# GDEnvSensorNode_1_4g.net
KiCad netlist of a schematic drawn in EAGLE
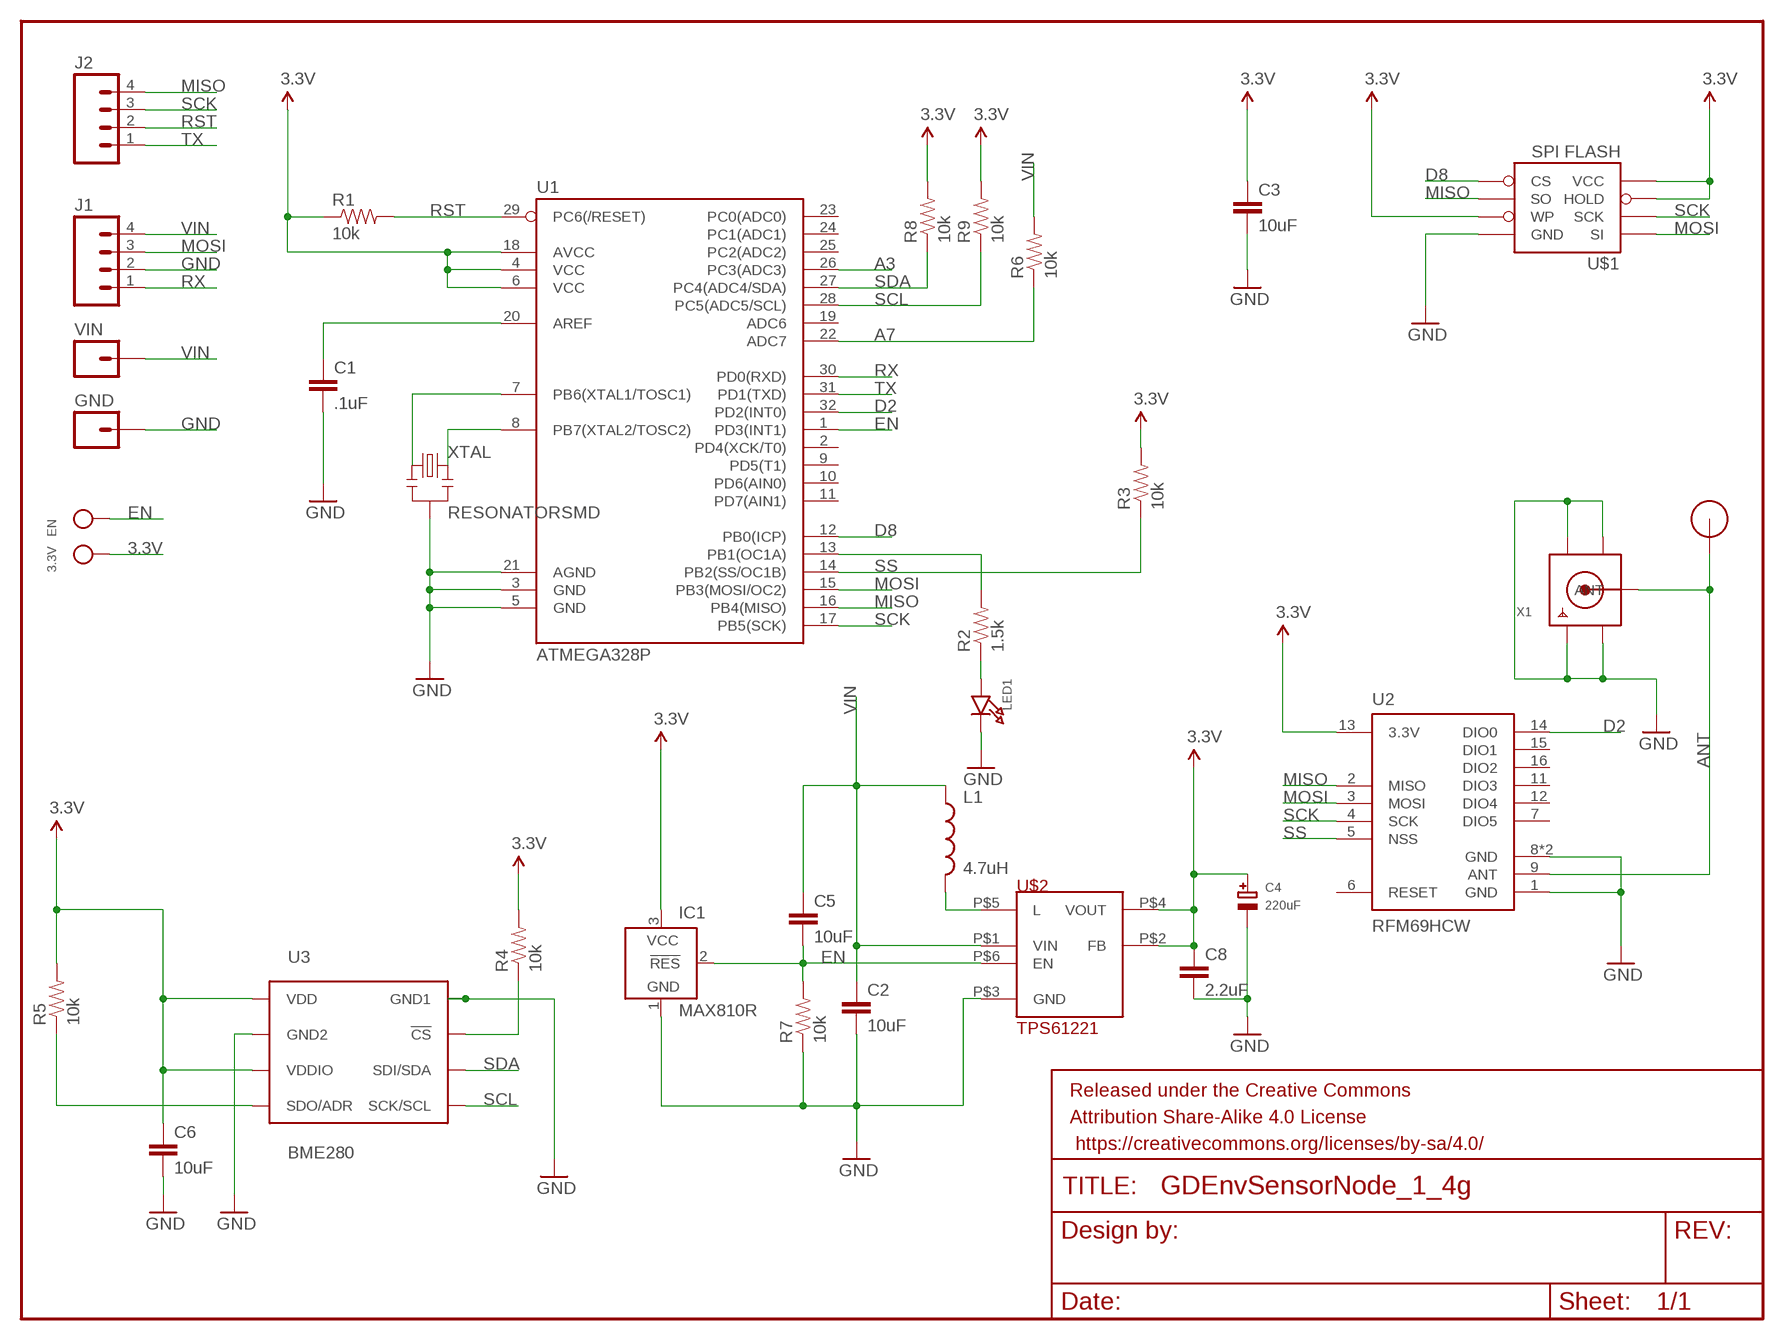
[diagram p0: schematic, sheet 1]

(export (version "E")
  (design (tool "Eeschema 10.0.6"))
  (components
    (comp (ref "3.3V")
      (value "TESTPOINTROUND1MM")
      (footprint "eagle-import:TESTPOINT_ROUND_1MM")
      (libsource (lib "eagle-import") (part "TESTPOINTROUND1MM"))
    )
    (comp (ref "C1")
      (value ".1uF")
      (footprint "eagle-import:0805")
      (libsource (lib "eagle-import") (part "CAP0805"))
    )
    (comp (ref "C2")
      (value "10uF")
      (footprint "eagle-import:0805")
      (libsource (lib "eagle-import") (part "CAP0805"))
    )
    (comp (ref "C3")
      (value "10uF")
      (footprint "eagle-import:0805")
      (libsource (lib "eagle-import") (part "CAP0805"))
    )
    (comp (ref "C4")
      (value "220uF")
      (footprint "eagle-import:EIA7343-31_D-R")
      (libsource (lib "eagle-import") (part "CAP_TANTALUMD/7343_REFLOW"))
    )
    (comp (ref "C5")
      (value "10uF")
      (footprint "eagle-import:0805")
      (libsource (lib "eagle-import") (part "CAP0805"))
    )
    (comp (ref "C6")
      (value "10uF")
      (footprint "eagle-import:0805")
      (libsource (lib "eagle-import") (part "CAP0805"))
    )
    (comp (ref "C8")
      (value "2.2uF")
      (footprint "eagle-import:0805")
      (libsource (lib "eagle-import") (part "CAP0805"))
    )
    (comp (ref "EN")
      (value "TESTPOINTROUND1MM")
      (footprint "eagle-import:TESTPOINT_ROUND_1MM")
      (libsource (lib "eagle-import") (part "TESTPOINTROUND1MM"))
    )
    (comp (ref "FRAME1")
      (value "FRAME-LETTER")
      (footprint "eagle-import:CREATIVE_COMMONS")
      (libsource (lib "eagle-import") (part "FRAME-LETTER"))
    )
    (comp (ref "GND")
      (value "M01PTH_2MM")
      (footprint "eagle-import:1X01_2MM")
      (libsource (lib "eagle-import") (part "M01PTH_2MM"))
    )
    (comp (ref "IC1")
      (value "MAX810R")
      (footprint "eagle-import:SOT23B-3")
      (fields (field (name "MF") "MICROCHIP") (field (name "MPN") "TCM809MENB713"))
      (libsource (lib "eagle-import") (part "TCM809"))
    )
    (comp (ref "J1")
      (value "M04PTH")
      (footprint "eagle-import:1X04")
      (libsource (lib "eagle-import") (part "M04PTH"))
    )
    (comp (ref "J2")
      (value "M04PTH")
      (footprint "eagle-import:1X04")
      (libsource (lib "eagle-import") (part "M04PTH"))
    )
    (comp (ref "L1")
      (value "4.7uH")
      (footprint "eagle-import:1210")
      (libsource (lib "eagle-import") (part "INDUCTOR1210"))
    )
    (comp (ref "LED1")
      (value "LED0805")
      (footprint "eagle-import:CHIPLED_0805")
      (libsource (lib "eagle-import") (part "LED0805"))
    )
    (comp (ref "R1")
      (value "10k")
      (footprint "eagle-import:0805")
      (libsource (lib "eagle-import") (part "RESISTOR0805-RES"))
    )
    (comp (ref "R2")
      (value "1.5k")
      (footprint "eagle-import:0805")
      (libsource (lib "eagle-import") (part "RESISTOR0805-RES"))
    )
    (comp (ref "R3")
      (value "10k")
      (footprint "eagle-import:0805")
      (libsource (lib "eagle-import") (part "RESISTOR0805-RES"))
    )
    (comp (ref "R4")
      (value "10k")
      (footprint "eagle-import:0805")
      (libsource (lib "eagle-import") (part "RESISTOR0805-RES"))
    )
    (comp (ref "R5")
      (value "10k")
      (footprint "eagle-import:0805")
      (libsource (lib "eagle-import") (part "RESISTOR0805-RES"))
    )
    (comp (ref "R6")
      (value "10k")
      (footprint "eagle-import:0805")
      (libsource (lib "eagle-import") (part "RESISTOR0805-RES"))
    )
    (comp (ref "R7")
      (value "10k")
      (footprint "eagle-import:0805")
      (libsource (lib "eagle-import") (part "RESISTOR0805-RES"))
    )
    (comp (ref "R8")
      (value "10k")
      (footprint "eagle-import:0805")
      (libsource (lib "eagle-import") (part "RESISTOR0805-RES"))
    )
    (comp (ref "R9")
      (value "10k")
      (footprint "eagle-import:0805")
      (libsource (lib "eagle-import") (part "RESISTOR0805-RES"))
    )
    (comp (ref "U$1")
      (value "SPI FLASH")
      (footprint "eagle-import:SO08")
      (libsource (lib "eagle-import") (part "AT25F512BJEDEC_3.9MM"))
    )
    (comp (ref "U$2")
      (value "TPS61221")
      (footprint "eagle-import:TPS61221")
      (fields (field (name "MF") "Texas Instruments"))
      (libsource (lib "eagle-import") (part "TPS61221"))
    )
    (comp (ref "U$4")
      (value "RFM12B_ANTENNA")
      (footprint "eagle-import:RFM12B-ANTENNA")
      (libsource (lib "eagle-import") (part "RFM12B_ANTENNA"))
    )
    (comp (ref "U1")
      (value "ATMEGA328P")
      (footprint "eagle-import:TQFP32-08")
      (libsource (lib "eagle-import") (part "ATMEGA328P_TQFP"))
    )
    (comp (ref "U2")
      (value "RFM69HCW")
      (footprint "eagle-import:RFM69HCW-XXXS2")
      (libsource (lib "eagle-import") (part "RFM69HCW"))
    )
    (comp (ref "U3")
      (value "BME280")
      (footprint "eagle-import:BME280_LGA")
      (libsource (lib "eagle-import") (part "BME280"))
    )
    (comp (ref "VIN")
      (value "M01PTH_2MM")
      (footprint "eagle-import:1X01_2MM")
      (libsource (lib "eagle-import") (part "M01PTH_2MM"))
    )
    (comp (ref "X1")
      (value "SMACONNECTOR_EDGE_UFL")
      (footprint "eagle-import:SMA_EDGELAUNCH_UFL")
      (libsource (lib "eagle-import") (part "SMACONNECTOR_EDGE_UFL"))
    )
    (comp (ref "XTAL")
      (value "RESONATORSMD")
      (footprint "eagle-import:RESONATOR-SMD")
      (libsource (lib "eagle-import") (part "RESONATORSMD"))
    )
  )
  (nets
    (net (code "1") (name "/A3") (class "Default")
      (node (ref "U1") (pin "26") (pinfunction "PC3(ADC3)_26") (pintype "bidirectional"))
    )
    (net (code "2") (name "/A7") (class "Default")
      (node (ref "R6") (pin "1") (pinfunction "1_1") (pintype "passive"))
      (node (ref "U1") (pin "22") (pinfunction "ADC7_22") (pintype "bidirectional"))
    )
    (net (code "3") (name "/ANT") (class "Default")
      (node (ref "U$4") (pin "P$1") (pinfunction "1_P$1") (pintype "bidirectional"))
      (node (ref "U2") (pin "9") (pinfunction "ANT_9") (pintype "passive"))
      (node (ref "X1") (pin "P") (pinfunction "ANT_P") (pintype "bidirectional"))
    )
    (net (code "4") (name "/D2") (class "Default")
      (node (ref "U1") (pin "32") (pinfunction "PD2(INT0)_32") (pintype "bidirectional"))
      (node (ref "U2") (pin "14") (pinfunction "DIO0_14") (pintype "bidirectional"))
    )
    (net (code "5") (name "/D8") (class "Default")
      (node (ref "U$1") (pin "1_CS") (pinfunction "CS_1_CS") (pintype "bidirectional"))
      (node (ref "U1") (pin "12") (pinfunction "PB0(ICP)_12") (pintype "bidirectional"))
    )
    (net (code "6") (name "/EN") (class "Default")
      (node (ref "C5") (pin "2") (pinfunction "2_2") (pintype "passive"))
      (node (ref "EN") (pin "P$1") (pinfunction "P$1_P$1") (pintype "bidirectional"))
      (node (ref "IC1") (pin "2") (pinfunction "~{RES}_2") (pintype "output"))
      (node (ref "R7") (pin "2") (pinfunction "2_2") (pintype "passive"))
      (node (ref "U$2") (pin "P$6") (pinfunction "EN_P$6") (pintype "bidirectional"))
      (node (ref "U1") (pin "1") (pinfunction "PD3(INT1)_1") (pintype "bidirectional"))
    )
    (net (code "7") (name "/MISO") (class "Default")
      (node (ref "J2") (pin "4") (pinfunction "4_4") (pintype "passive"))
      (node (ref "U$1") (pin "2_SO") (pinfunction "SO_2_SO") (pintype "bidirectional"))
      (node (ref "U1") (pin "16") (pinfunction "PB4(MISO)_16") (pintype "bidirectional"))
      (node (ref "U2") (pin "2") (pinfunction "MISO_2") (pintype "bidirectional"))
    )
    (net (code "8") (name "/MOSI") (class "Default")
      (node (ref "J1") (pin "3") (pinfunction "3_3") (pintype "passive"))
      (node (ref "U$1") (pin "5_SI") (pinfunction "SI_5_SI") (pintype "bidirectional"))
      (node (ref "U1") (pin "15") (pinfunction "PB3(MOSI/OC2)_15") (pintype "bidirectional"))
      (node (ref "U2") (pin "3") (pinfunction "MOSI_3") (pintype "input"))
    )
    (net (code "9") (name "/RST") (class "Default")
      (node (ref "J2") (pin "2") (pinfunction "2_2") (pintype "passive"))
      (node (ref "R1") (pin "2") (pinfunction "2_2") (pintype "passive"))
      (node (ref "U1") (pin "29") (pinfunction "PC6(/RESET)_29") (pintype "bidirectional"))
    )
    (net (code "10") (name "/RX") (class "Default")
      (node (ref "J1") (pin "1") (pinfunction "1_1") (pintype "passive"))
      (node (ref "U1") (pin "30") (pinfunction "PD0(RXD)_30") (pintype "bidirectional"))
    )
    (net (code "11") (name "/SCK") (class "Default")
      (node (ref "J2") (pin "3") (pinfunction "3_3") (pintype "passive"))
      (node (ref "U$1") (pin "6_SCK") (pinfunction "SCK_6_SCK") (pintype "bidirectional"))
      (node (ref "U1") (pin "17") (pinfunction "PB5(SCK)_17") (pintype "bidirectional"))
      (node (ref "U2") (pin "4") (pinfunction "SCK_4") (pintype "input"))
    )
    (net (code "12") (name "/SCL") (class "Default")
      (node (ref "R9") (pin "1") (pinfunction "1_1") (pintype "passive"))
      (node (ref "U1") (pin "28") (pinfunction "PC5(ADC5/SCL)_28") (pintype "bidirectional"))
      (node (ref "U3") (pin "P$4") (pinfunction "SCK/SCL_P$4") (pintype "bidirectional"))
    )
    (net (code "13") (name "/SDA") (class "Default")
      (node (ref "R8") (pin "1") (pinfunction "1_1") (pintype "passive"))
      (node (ref "U1") (pin "27") (pinfunction "PC4(ADC4/SDA)_27") (pintype "bidirectional"))
      (node (ref "U3") (pin "P$3") (pinfunction "SDI/SDA_P$3") (pintype "bidirectional"))
    )
    (net (code "14") (name "/SS") (class "Default")
      (node (ref "R3") (pin "1") (pinfunction "1_1") (pintype "passive"))
      (node (ref "U1") (pin "14") (pinfunction "PB2(SS/OC1B)_14") (pintype "bidirectional"))
      (node (ref "U2") (pin "5") (pinfunction "NSS_5") (pintype "input"))
    )
    (net (code "15") (name "/TX") (class "Default")
      (node (ref "J2") (pin "1") (pinfunction "1_1") (pintype "passive"))
      (node (ref "U1") (pin "31") (pinfunction "PD1(TXD)_31") (pintype "bidirectional"))
    )
    (net (code "16") (name "/VIN") (class "Default")
      (node (ref "C2") (pin "1") (pinfunction "1_1") (pintype "passive"))
      (node (ref "C5") (pin "1") (pinfunction "1_1") (pintype "passive"))
      (node (ref "J1") (pin "4") (pinfunction "4_4") (pintype "passive"))
      (node (ref "L1") (pin "1") (pinfunction "1_1") (pintype "passive"))
      (node (ref "R6") (pin "2") (pinfunction "2_2") (pintype "passive"))
      (node (ref "U$2") (pin "P$1") (pinfunction "VIN_P$1") (pintype "bidirectional"))
      (node (ref "VIN") (pin "1") (pinfunction "1_1") (pintype "passive"))
    )
    (net (code "17") (name "3.3V") (class "Default")
      (node (ref "3.3V") (pin "P$1") (pinfunction "P$1_P$1") (pintype "bidirectional"))
      (node (ref "C3") (pin "1") (pinfunction "1_1") (pintype "passive"))
      (node (ref "C4") (pin "+") (pinfunction "+_+") (pintype "passive"))
      (node (ref "C6") (pin "1") (pinfunction "1_1") (pintype "passive"))
      (node (ref "C8") (pin "1") (pinfunction "1_1") (pintype "passive"))
      (node (ref "IC1") (pin "3") (pinfunction "VCC_3") (pintype "power_in"))
      (node (ref "R1") (pin "1") (pinfunction "1_1") (pintype "passive"))
      (node (ref "R3") (pin "2") (pinfunction "2_2") (pintype "passive"))
      (node (ref "R4") (pin "2") (pinfunction "2_2") (pintype "passive"))
      (node (ref "R5") (pin "2") (pinfunction "2_2") (pintype "passive"))
      (node (ref "R8") (pin "2") (pinfunction "2_2") (pintype "passive"))
      (node (ref "R9") (pin "2") (pinfunction "2_2") (pintype "passive"))
      (node (ref "U$1") (pin "3_WP") (pinfunction "WP_3_WP") (pintype "bidirectional"))
      (node (ref "U$1") (pin "7_HOLD") (pinfunction "HOLD_7_HOLD") (pintype "bidirectional"))
      (node (ref "U$1") (pin "8_VCC") (pinfunction "VCC_8_VCC") (pintype "bidirectional"))
      (node (ref "U$2") (pin "P$2") (pinfunction "FB_P$2") (pintype "bidirectional"))
      (node (ref "U$2") (pin "P$4") (pinfunction "VOUT_P$4") (pintype "bidirectional"))
      (node (ref "U1") (pin "18") (pinfunction "AVCC_18") (pintype "bidirectional"))
      (node (ref "U1") (pin "4") (pinfunction "VCC_4") (pintype "bidirectional"))
      (node (ref "U1") (pin "6") (pinfunction "VCC_6") (pintype "bidirectional"))
      (node (ref "U2") (pin "13") (pinfunction "3.3V_13") (pintype "power_in"))
      (node (ref "U3") (pin "P$6") (pinfunction "VDDIO_P$6") (pintype "bidirectional"))
      (node (ref "U3") (pin "P$8") (pinfunction "VDD_P$8") (pintype "bidirectional"))
    )
    (net (code "18") (name "GND") (class "Default")
      (node (ref "C1") (pin "2") (pinfunction "2_2") (pintype "passive"))
      (node (ref "C2") (pin "2") (pinfunction "2_2") (pintype "passive"))
      (node (ref "C3") (pin "2") (pinfunction "2_2") (pintype "passive"))
      (node (ref "C4") (pin "-") (pinfunction "-_-") (pintype "passive"))
      (node (ref "C6") (pin "2") (pinfunction "2_2") (pintype "passive"))
      (node (ref "C8") (pin "2") (pinfunction "2_2") (pintype "passive"))
      (node (ref "GND") (pin "1") (pinfunction "1_1") (pintype "passive"))
      (node (ref "IC1") (pin "1") (pinfunction "GND_1") (pintype "power_in"))
      (node (ref "J1") (pin "2") (pinfunction "2_2") (pintype "passive"))
      (node (ref "LED1") (pin "C") (pinfunction "C_C") (pintype "passive"))
      (node (ref "R7") (pin "1") (pinfunction "1_1") (pintype "passive"))
      (node (ref "U$1") (pin "4_GND") (pinfunction "GND_4_GND") (pintype "bidirectional"))
      (node (ref "U$2") (pin "P$3") (pinfunction "GND_P$3") (pintype "bidirectional"))
      (node (ref "U1") (pin "21") (pinfunction "AGND_21") (pintype "bidirectional"))
      (node (ref "U1") (pin "3") (pinfunction "GND_3") (pintype "bidirectional"))
      (node (ref "U1") (pin "5") (pinfunction "GND_5") (pintype "bidirectional"))
      (node (ref "U2") (pin "1") (pinfunction "GND_1") (pintype "power_in"))
      (node (ref "U2") (pin "10") (pinfunction "GND_10") (pintype "power_in"))
      (node (ref "U2") (pin "8") (pinfunction "GND_8") (pintype "power_in"))
      (node (ref "U3") (pin "P$1") (pinfunction "GND1_P$1") (pintype "bidirectional"))
      (node (ref "U3") (pin "P$7") (pinfunction "GND2_P$7") (pintype "bidirectional"))
      (node (ref "X1") (pin "GND@1") (pinfunction "GND1_GND@1") (pintype "power_in"))
      (node (ref "X1") (pin "GND@2") (pinfunction "GND2_GND@2") (pintype "power_in"))
      (node (ref "X1") (pin "GND@3") (pinfunction "GND3_GND@3") (pintype "power_in"))
      (node (ref "X1") (pin "GND@4") (pinfunction "GND4_GND@4") (pintype "power_in"))
      (node (ref "XTAL") (pin "2") (pinfunction "2_2") (pintype "passive"))
    )
    (net (code "19") (name "Net-(LED1-PadA)") (class "Default")
      (node (ref "LED1") (pin "A") (pinfunction "A_A") (pintype "passive"))
      (node (ref "R2") (pin "1") (pinfunction "1_1") (pintype "passive"))
    )
    (net (code "20") (name "Net-(U$2-L)") (class "Default")
      (node (ref "L1") (pin "2") (pinfunction "2_2") (pintype "passive"))
      (node (ref "U$2") (pin "P$5") (pinfunction "L_P$5") (pintype "bidirectional"))
    )
    (net (code "21") (name "Net-(U1-AREF)") (class "Default")
      (node (ref "C1") (pin "1") (pinfunction "1_1") (pintype "passive"))
      (node (ref "U1") (pin "20") (pinfunction "AREF_20") (pintype "bidirectional"))
    )
    (net (code "22") (name "Net-(U1-PB1(OC1A))") (class "Default")
      (node (ref "R2") (pin "2") (pinfunction "2_2") (pintype "passive"))
      (node (ref "U1") (pin "13") (pinfunction "PB1(OC1A)_13") (pintype "bidirectional"))
    )
    (net (code "23") (name "Net-(U1-PB6(XTAL1{slash}TOSC1))") (class "Default")
      (node (ref "U1") (pin "7") (pinfunction "PB6(XTAL1/TOSC1)_7") (pintype "bidirectional"))
      (node (ref "XTAL") (pin "1") (pinfunction "1_1") (pintype "passive"))
    )
    (net (code "24") (name "Net-(U1-PB7(XTAL2{slash}TOSC2))") (class "Default")
      (node (ref "U1") (pin "8") (pinfunction "PB7(XTAL2/TOSC2)_8") (pintype "bidirectional"))
      (node (ref "XTAL") (pin "3") (pinfunction "3_3") (pintype "passive"))
    )
    (net (code "25") (name "Net-(U3-SDO{slash}ADR)") (class "Default")
      (node (ref "R5") (pin "1") (pinfunction "1_1") (pintype "passive"))
      (node (ref "U3") (pin "P$5") (pinfunction "SDO/ADR_P$5") (pintype "bidirectional"))
    )
    (net (code "26") (name "Net-(U3-~{CS})") (class "Default")
      (node (ref "R4") (pin "1") (pinfunction "1_1") (pintype "passive"))
      (node (ref "U3") (pin "P$2") (pinfunction "~{CS}_P$2") (pintype "bidirectional"))
    )
    (net (code "27") (name "unconnected-(U1-ADC6-Pad19)") (class "Default")
      (node (ref "U1") (pin "19") (pinfunction "ADC6_19") (pintype "bidirectional"))
    )
    (net (code "28") (name "unconnected-(U1-PC0(ADC0)-Pad23)") (class "Default")
      (node (ref "U1") (pin "23") (pinfunction "PC0(ADC0)_23") (pintype "bidirectional"))
    )
    (net (code "29") (name "unconnected-(U1-PC1(ADC1)-Pad24)") (class "Default")
      (node (ref "U1") (pin "24") (pinfunction "PC1(ADC1)_24") (pintype "bidirectional"))
    )
    (net (code "30") (name "unconnected-(U1-PC2(ADC2)-Pad25)") (class "Default")
      (node (ref "U1") (pin "25") (pinfunction "PC2(ADC2)_25") (pintype "bidirectional"))
    )
    (net (code "31") (name "unconnected-(U1-PD4(XCK{slash}T0)-Pad2)") (class "Default")
      (node (ref "U1") (pin "2") (pinfunction "PD4(XCK/T0)_2") (pintype "bidirectional"))
    )
    (net (code "32") (name "unconnected-(U1-PD5(T1)-Pad9)") (class "Default")
      (node (ref "U1") (pin "9") (pinfunction "PD5(T1)_9") (pintype "bidirectional"))
    )
    (net (code "33") (name "unconnected-(U1-PD6(AIN0)-Pad10)") (class "Default")
      (node (ref "U1") (pin "10") (pinfunction "PD6(AIN0)_10") (pintype "bidirectional"))
    )
    (net (code "34") (name "unconnected-(U1-PD7(AIN1)-Pad11)") (class "Default")
      (node (ref "U1") (pin "11") (pinfunction "PD7(AIN1)_11") (pintype "bidirectional"))
    )
    (net (code "35") (name "unconnected-(U2-DIO1-Pad15)") (class "Default")
      (node (ref "U2") (pin "15") (pinfunction "DIO1_15") (pintype "bidirectional"))
    )
    (net (code "36") (name "unconnected-(U2-DIO2-Pad16)") (class "Default")
      (node (ref "U2") (pin "16") (pinfunction "DIO2_16") (pintype "bidirectional"))
    )
    (net (code "37") (name "unconnected-(U2-DIO3-Pad11)") (class "Default")
      (node (ref "U2") (pin "11") (pinfunction "DIO3_11") (pintype "bidirectional"))
    )
    (net (code "38") (name "unconnected-(U2-DIO4-Pad12)") (class "Default")
      (node (ref "U2") (pin "12") (pinfunction "DIO4_12") (pintype "bidirectional"))
    )
    (net (code "39") (name "unconnected-(U2-DIO5-Pad7)") (class "Default")
      (node (ref "U2") (pin "7") (pinfunction "DIO5_7") (pintype "bidirectional"))
    )
    (net (code "40") (name "unconnected-(U2-RESET-Pad6)") (class "Default")
      (node (ref "U2") (pin "6") (pinfunction "RESET_6") (pintype "input"))
    )
  )
)
